# rc-light-controller-tlc5940-lpc812.net
KiCad netlist of a schematic drawn in EAGLE
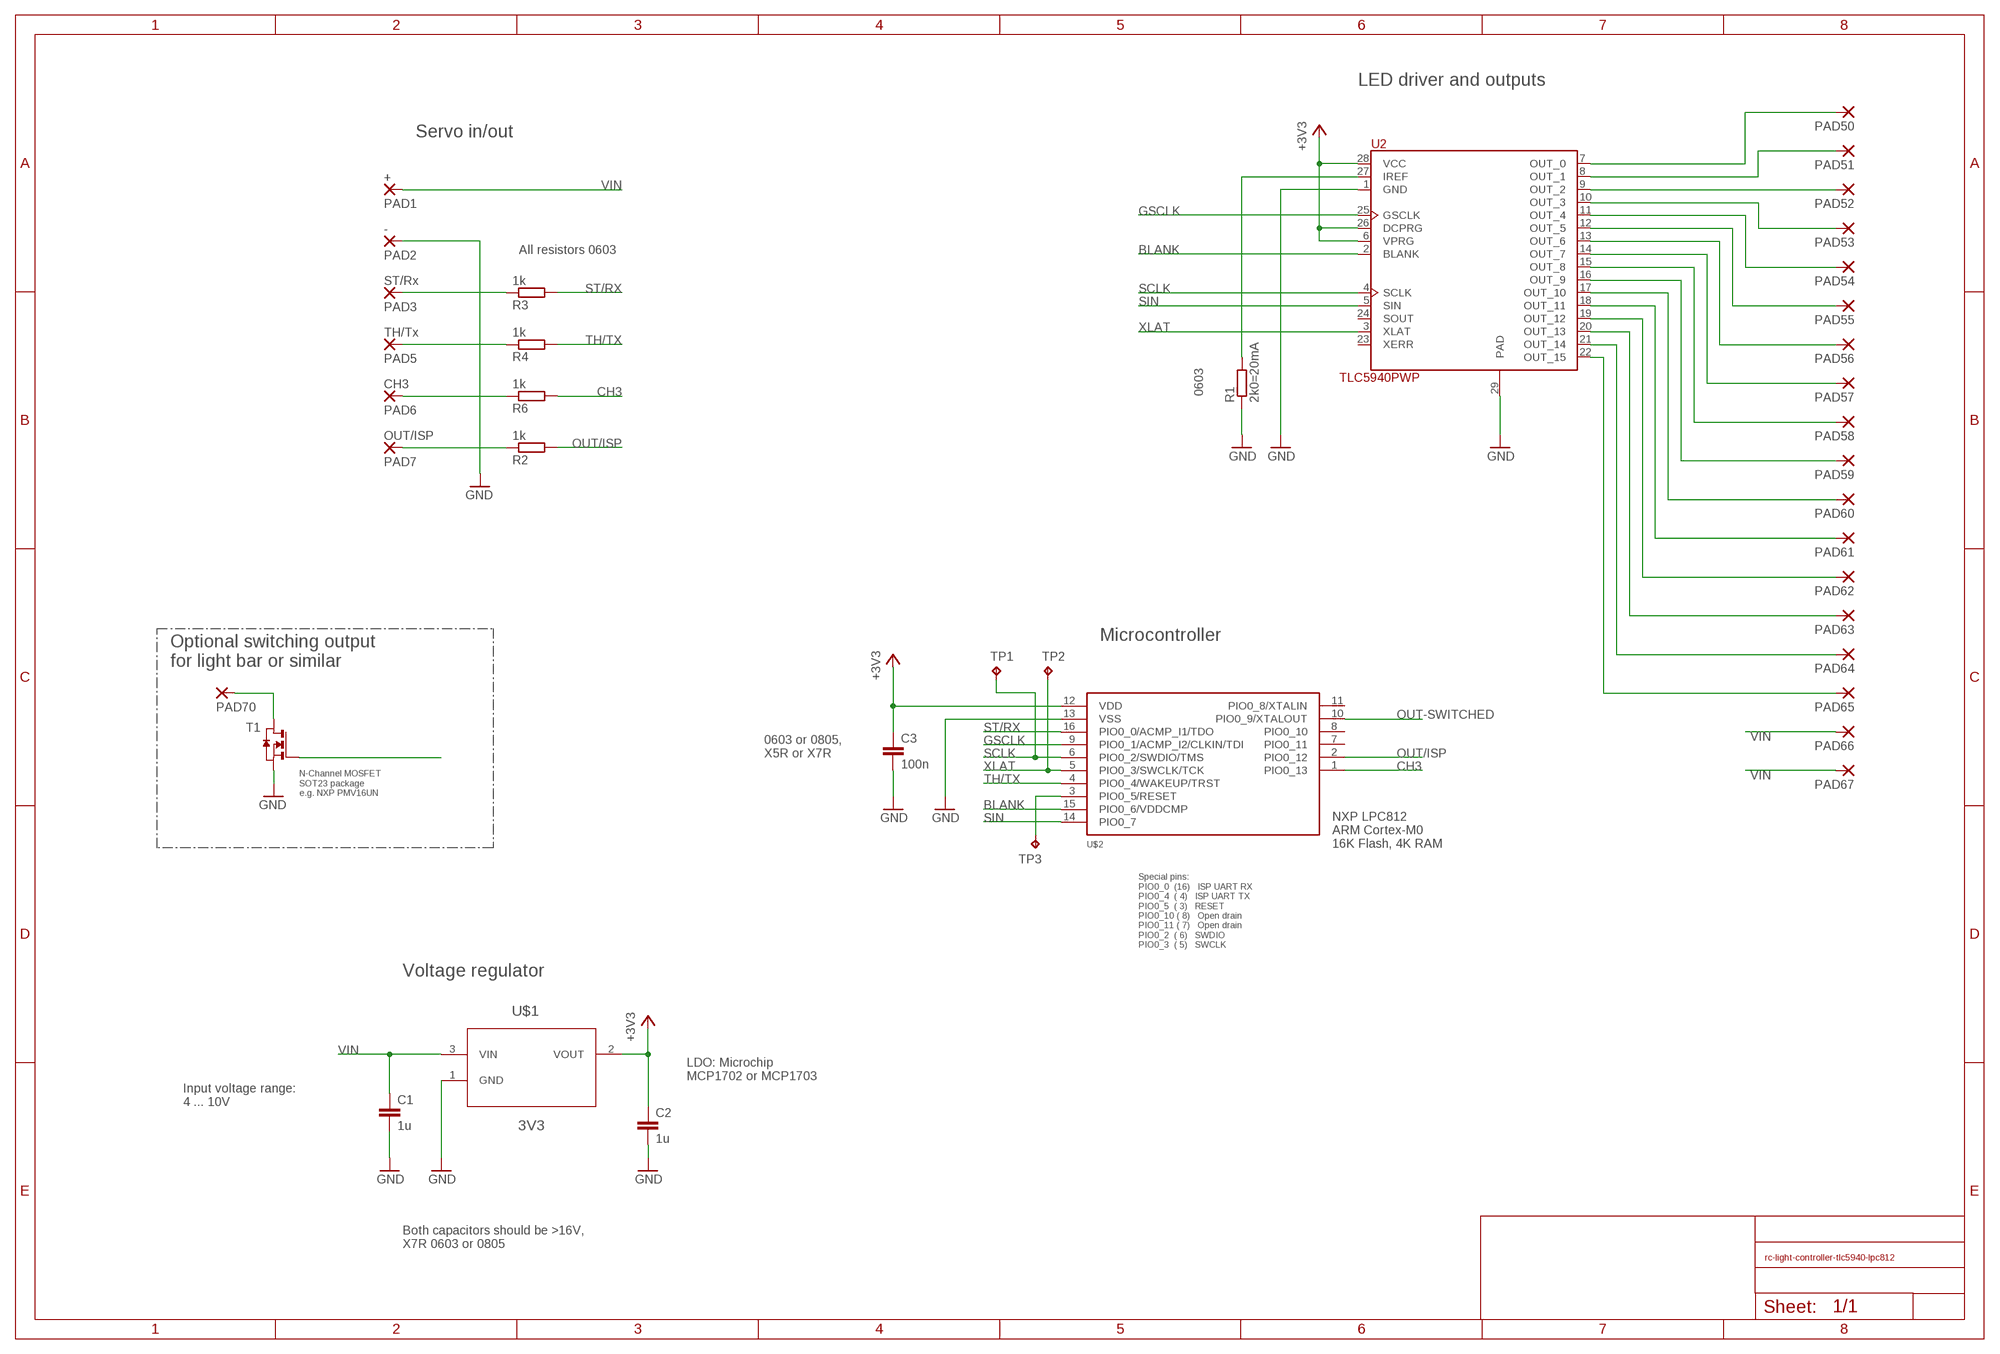
[diagram p0: schematic, sheet 1]

(export (version "E")
  (design (tool "Eeschema 10.0.6"))
  (components
    (comp (ref "C1")
      (value "1u")
      (footprint "eagle-import:C0805")
      (libsource (lib "eagle-import") (part "C-EUC0805"))
    )
    (comp (ref "C2")
      (value "1u")
      (footprint "eagle-import:C0805")
      (libsource (lib "eagle-import") (part "C-EUC0805"))
    )
    (comp (ref "C3")
      (value "100n")
      (footprint "eagle-import:C0805")
      (libsource (lib "eagle-import") (part "C-EUC0805"))
    )
    (comp (ref "PAD1")
      (value "+")
      (footprint "eagle-import:SMD80X120")
      (libsource (lib "eagle-import") (part "SDM80X120"))
    )
    (comp (ref "PAD2")
      (value "-")
      (footprint "eagle-import:SMD80X120")
      (libsource (lib "eagle-import") (part "SDM80X120"))
    )
    (comp (ref "PAD3")
      (value "ST/Rx")
      (footprint "eagle-import:SMD80X120")
      (libsource (lib "eagle-import") (part "SDM80X120"))
    )
    (comp (ref "PAD5")
      (value "TH/Tx")
      (footprint "eagle-import:SMD80X120")
      (libsource (lib "eagle-import") (part "SDM80X120"))
    )
    (comp (ref "PAD6")
      (value "CH3")
      (footprint "eagle-import:SMD80X120")
      (libsource (lib "eagle-import") (part "SDM80X120"))
    )
    (comp (ref "PAD7")
      (value "OUT/ISP")
      (footprint "eagle-import:SMD80X120")
      (libsource (lib "eagle-import") (part "SDM80X120"))
    )
    (comp (ref "PAD50")
      (value "SMD50X100")
      (footprint "eagle-import:SMD50X100")
      (libsource (lib "eagle-import") (part "SMD50X100"))
    )
    (comp (ref "PAD51")
      (value "SMD50X100")
      (footprint "eagle-import:SMD50X100")
      (libsource (lib "eagle-import") (part "SMD50X100"))
    )
    (comp (ref "PAD52")
      (value "SMD50X100")
      (footprint "eagle-import:SMD50X100")
      (libsource (lib "eagle-import") (part "SMD50X100"))
    )
    (comp (ref "PAD53")
      (value "SMD50X100")
      (footprint "eagle-import:SMD50X100")
      (libsource (lib "eagle-import") (part "SMD50X100"))
    )
    (comp (ref "PAD54")
      (value "SMD50X100")
      (footprint "eagle-import:SMD50X100")
      (libsource (lib "eagle-import") (part "SMD50X100"))
    )
    (comp (ref "PAD55")
      (value "SMD50X100")
      (footprint "eagle-import:SMD50X100")
      (libsource (lib "eagle-import") (part "SMD50X100"))
    )
    (comp (ref "PAD56")
      (value "SMD50X100")
      (footprint "eagle-import:SMD50X100")
      (libsource (lib "eagle-import") (part "SMD50X100"))
    )
    (comp (ref "PAD57")
      (value "SMD50X100")
      (footprint "eagle-import:SMD50X100")
      (libsource (lib "eagle-import") (part "SMD50X100"))
    )
    (comp (ref "PAD58")
      (value "SMD50X100")
      (footprint "eagle-import:SMD50X100")
      (libsource (lib "eagle-import") (part "SMD50X100"))
    )
    (comp (ref "PAD59")
      (value "SMD50X100")
      (footprint "eagle-import:SMD50X100")
      (libsource (lib "eagle-import") (part "SMD50X100"))
    )
    (comp (ref "PAD60")
      (value "SMD50X100")
      (footprint "eagle-import:SMD50X100")
      (libsource (lib "eagle-import") (part "SMD50X100"))
    )
    (comp (ref "PAD61")
      (value "SMD50X100")
      (footprint "eagle-import:SMD50X100")
      (libsource (lib "eagle-import") (part "SMD50X100"))
    )
    (comp (ref "PAD62")
      (value "SMD50X100")
      (footprint "eagle-import:SMD50X100")
      (libsource (lib "eagle-import") (part "SMD50X100"))
    )
    (comp (ref "PAD63")
      (value "SMD50X100")
      (footprint "eagle-import:SMD50X100")
      (libsource (lib "eagle-import") (part "SMD50X100"))
    )
    (comp (ref "PAD64")
      (value "SMD50X100")
      (footprint "eagle-import:SMD50X100")
      (libsource (lib "eagle-import") (part "SMD50X100"))
    )
    (comp (ref "PAD65")
      (value "SMD50X100")
      (footprint "eagle-import:SMD50X100")
      (libsource (lib "eagle-import") (part "SMD50X100"))
    )
    (comp (ref "PAD66")
      (value "SMD50X100")
      (footprint "eagle-import:SMD50X100")
      (libsource (lib "eagle-import") (part "SMD50X100"))
    )
    (comp (ref "PAD67")
      (value "SMD50X100")
      (footprint "eagle-import:SMD50X100")
      (libsource (lib "eagle-import") (part "SMD50X100"))
    )
    (comp (ref "PAD70")
      (value "SMD50X100")
      (footprint "eagle-import:SMD50X100")
      (libsource (lib "eagle-import") (part "SMD50X100"))
    )
    (comp (ref "R1")
      (value "2k0=20mA")
      (footprint "eagle-import:R0805")
      (libsource (lib "eagle-import") (part "R-EU_R0805"))
    )
    (comp (ref "R2")
      (value "1k")
      (footprint "eagle-import:R0603")
      (libsource (lib "eagle-import") (part "R-EU_R0603"))
    )
    (comp (ref "R3")
      (value "1k")
      (footprint "eagle-import:R0603")
      (libsource (lib "eagle-import") (part "R-EU_R0603"))
    )
    (comp (ref "R4")
      (value "1k")
      (footprint "eagle-import:R0603")
      (libsource (lib "eagle-import") (part "R-EU_R0603"))
    )
    (comp (ref "R6")
      (value "1k")
      (footprint "eagle-import:R0603")
      (libsource (lib "eagle-import") (part "R-EU_R0603"))
    )
    (comp (ref "T1")
      (value "NMOSSOT23")
      (footprint "eagle-import:SOT-23")
      (libsource (lib "eagle-import") (part "NMOSSOT23"))
    )
    (comp (ref "TP1")
      (value "SWDIO")
      (footprint "eagle-import:TP10R")
      (libsource (lib "eagle-import") (part "TPTP10R"))
    )
    (comp (ref "TP2")
      (value "SWCLK")
      (footprint "eagle-import:TP10R")
      (libsource (lib "eagle-import") (part "TPTP10R"))
    )
    (comp (ref "TP3")
      (value "RESET")
      (footprint "eagle-import:TP10R")
      (libsource (lib "eagle-import") (part "TPTP10R"))
    )
    (comp (ref "U$1")
      (value "3V3")
      (footprint "eagle-import:SOT95P300X145-3N")
      (fields (field (name "MPN") "MCP1703T-3302E/CB"))
      (libsource (lib "eagle-import") (part "MCP1703T-3302E/CB"))
    )
    (comp (ref "U$2")
      (value "LPC812")
      (footprint "eagle-import:TSSOP16")
      (libsource (lib "eagle-import") (part "LPC812M101JDH16"))
    )
    (comp (ref "U2")
      (value "TLC5940PWP")
      (footprint "eagle-import:SOP65P640X120-29N")
      (libsource (lib "eagle-import") (part "TLC5940PWP"))
    )
  )
  (nets
    (net (code "1") (name "+3V3") (class "Default")
      (node (ref "C2") (pin "1") (pinfunction "1_1") (pintype "passive"))
      (node (ref "C3") (pin "1") (pinfunction "1_1") (pintype "passive"))
      (node (ref "U$1") (pin "2") (pinfunction "VOUT_2") (pintype "output"))
      (node (ref "U$2") (pin "12") (pinfunction "VDD_12") (pintype "bidirectional"))
      (node (ref "U2") (pin "26") (pinfunction "DCPRG_26") (pintype "input"))
      (node (ref "U2") (pin "28") (pinfunction "VCC_28") (pintype "power_in"))
      (node (ref "U2") (pin "6") (pinfunction "VPRG_6") (pintype "input"))
    )
    (net (code "2") (name "/BLANK") (class "Default")
      (node (ref "U$2") (pin "15") (pinfunction "PIO0_6/VDDCMP_15") (pintype "bidirectional"))
      (node (ref "U2") (pin "2") (pinfunction "BLANK_2") (pintype "input"))
    )
    (net (code "3") (name "/CH3") (class "Default")
      (node (ref "R6") (pin "2") (pinfunction "2_2") (pintype "passive"))
      (node (ref "U$2") (pin "1") (pinfunction "PIO0_13_1") (pintype "bidirectional"))
    )
    (net (code "4") (name "/GSCLK") (class "Default")
      (node (ref "U$2") (pin "9") (pinfunction "PIO0_1/ACMP_I2/CLKIN/TDI_9") (pintype "bidirectional"))
      (node (ref "U2") (pin "25") (pinfunction "GSCLK_25") (pintype "input"))
    )
    (net (code "5") (name "/OUT-SWITCHED") (class "Default")
      (node (ref "T1") (pin "3") (pinfunction "G_3") (pintype "passive"))
      (node (ref "U$2") (pin "10") (pinfunction "PIO0_9/XTALOUT_10") (pintype "bidirectional"))
    )
    (net (code "6") (name "/OUT{slash}ISP") (class "Default")
      (node (ref "R2") (pin "2") (pinfunction "2_2") (pintype "passive"))
      (node (ref "U$2") (pin "2") (pinfunction "PIO0_12_2") (pintype "bidirectional"))
    )
    (net (code "7") (name "/SCLK") (class "Default")
      (node (ref "TP1") (pin "TP") (pinfunction "TP_TP") (pintype "input"))
      (node (ref "U$2") (pin "6") (pinfunction "PIO0_2/SWDIO/TMS_6") (pintype "bidirectional"))
      (node (ref "U2") (pin "4") (pinfunction "SCLK_4") (pintype "input"))
    )
    (net (code "8") (name "/SIN") (class "Default")
      (node (ref "U$2") (pin "14") (pinfunction "PIO0_7_14") (pintype "bidirectional"))
      (node (ref "U2") (pin "5") (pinfunction "SIN_5") (pintype "input"))
    )
    (net (code "9") (name "/ST{slash}RX") (class "Default")
      (node (ref "R3") (pin "2") (pinfunction "2_2") (pintype "passive"))
      (node (ref "U$2") (pin "16") (pinfunction "PIO0_0/ACMP_I1/TDO_16") (pintype "bidirectional"))
    )
    (net (code "10") (name "/TH{slash}TX") (class "Default")
      (node (ref "R4") (pin "2") (pinfunction "2_2") (pintype "passive"))
      (node (ref "U$2") (pin "4") (pinfunction "PIO0_4/WAKEUP/TRST_4") (pintype "bidirectional"))
    )
    (net (code "11") (name "/VIN") (class "Default")
      (node (ref "C1") (pin "1") (pinfunction "1_1") (pintype "passive"))
      (node (ref "PAD1") (pin "1") (pinfunction "P_1") (pintype "passive"))
      (node (ref "PAD66") (pin "1") (pinfunction "P_1") (pintype "passive"))
      (node (ref "PAD67") (pin "1") (pinfunction "P_1") (pintype "passive"))
      (node (ref "U$1") (pin "3") (pinfunction "VIN_3") (pintype "input"))
    )
    (net (code "12") (name "/XLAT") (class "Default")
      (node (ref "TP2") (pin "TP") (pinfunction "TP_TP") (pintype "input"))
      (node (ref "U$2") (pin "5") (pinfunction "PIO0_3/SWCLK/TCK_5") (pintype "bidirectional"))
      (node (ref "U2") (pin "3") (pinfunction "XLAT_3") (pintype "input"))
    )
    (net (code "13") (name "GND") (class "Default")
      (node (ref "C1") (pin "2") (pinfunction "2_2") (pintype "passive"))
      (node (ref "C2") (pin "2") (pinfunction "2_2") (pintype "passive"))
      (node (ref "C3") (pin "2") (pinfunction "2_2") (pintype "passive"))
      (node (ref "PAD2") (pin "1") (pinfunction "P_1") (pintype "passive"))
      (node (ref "R1") (pin "1") (pinfunction "1_1") (pintype "passive"))
      (node (ref "T1") (pin "2") (pinfunction "S_2") (pintype "passive"))
      (node (ref "U$1") (pin "1") (pinfunction "GND_1") (pintype "passive"))
      (node (ref "U$2") (pin "13") (pinfunction "VSS_13") (pintype "bidirectional"))
      (node (ref "U2") (pin "1") (pinfunction "GND_1") (pintype "power_in"))
      (node (ref "U2") (pin "29") (pinfunction "PAD_29") (pintype "passive"))
    )
    (net (code "14") (name "Net-(PAD3-P)") (class "Default")
      (node (ref "PAD3") (pin "1") (pinfunction "P_1") (pintype "passive"))
      (node (ref "R3") (pin "1") (pinfunction "1_1") (pintype "passive"))
    )
    (net (code "15") (name "Net-(PAD5-P)") (class "Default")
      (node (ref "PAD5") (pin "1") (pinfunction "P_1") (pintype "passive"))
      (node (ref "R4") (pin "1") (pinfunction "1_1") (pintype "passive"))
    )
    (net (code "16") (name "Net-(PAD6-P)") (class "Default")
      (node (ref "PAD6") (pin "1") (pinfunction "P_1") (pintype "passive"))
      (node (ref "R6") (pin "1") (pinfunction "1_1") (pintype "passive"))
    )
    (net (code "17") (name "Net-(PAD7-P)") (class "Default")
      (node (ref "PAD7") (pin "1") (pinfunction "P_1") (pintype "passive"))
      (node (ref "R2") (pin "1") (pinfunction "1_1") (pintype "passive"))
    )
    (net (code "18") (name "Net-(PAD50-P)") (class "Default")
      (node (ref "PAD50") (pin "1") (pinfunction "P_1") (pintype "passive"))
      (node (ref "U2") (pin "7") (pinfunction "OUT_0_7") (pintype "output"))
    )
    (net (code "19") (name "Net-(PAD51-P)") (class "Default")
      (node (ref "PAD51") (pin "1") (pinfunction "P_1") (pintype "passive"))
      (node (ref "U2") (pin "8") (pinfunction "OUT_1_8") (pintype "output"))
    )
    (net (code "20") (name "Net-(PAD52-P)") (class "Default")
      (node (ref "PAD52") (pin "1") (pinfunction "P_1") (pintype "passive"))
      (node (ref "U2") (pin "9") (pinfunction "OUT_2_9") (pintype "output"))
    )
    (net (code "21") (name "Net-(PAD53-P)") (class "Default")
      (node (ref "PAD53") (pin "1") (pinfunction "P_1") (pintype "passive"))
      (node (ref "U2") (pin "10") (pinfunction "OUT_3_10") (pintype "output"))
    )
    (net (code "22") (name "Net-(PAD54-P)") (class "Default")
      (node (ref "PAD54") (pin "1") (pinfunction "P_1") (pintype "passive"))
      (node (ref "U2") (pin "11") (pinfunction "OUT_4_11") (pintype "output"))
    )
    (net (code "23") (name "Net-(PAD55-P)") (class "Default")
      (node (ref "PAD55") (pin "1") (pinfunction "P_1") (pintype "passive"))
      (node (ref "U2") (pin "12") (pinfunction "OUT_5_12") (pintype "output"))
    )
    (net (code "24") (name "Net-(PAD56-P)") (class "Default")
      (node (ref "PAD56") (pin "1") (pinfunction "P_1") (pintype "passive"))
      (node (ref "U2") (pin "13") (pinfunction "OUT_6_13") (pintype "output"))
    )
    (net (code "25") (name "Net-(PAD57-P)") (class "Default")
      (node (ref "PAD57") (pin "1") (pinfunction "P_1") (pintype "passive"))
      (node (ref "U2") (pin "14") (pinfunction "OUT_7_14") (pintype "output"))
    )
    (net (code "26") (name "Net-(PAD58-P)") (class "Default")
      (node (ref "PAD58") (pin "1") (pinfunction "P_1") (pintype "passive"))
      (node (ref "U2") (pin "15") (pinfunction "OUT_8_15") (pintype "output"))
    )
    (net (code "27") (name "Net-(PAD59-P)") (class "Default")
      (node (ref "PAD59") (pin "1") (pinfunction "P_1") (pintype "passive"))
      (node (ref "U2") (pin "16") (pinfunction "OUT_9_16") (pintype "output"))
    )
    (net (code "28") (name "Net-(PAD60-P)") (class "Default")
      (node (ref "PAD60") (pin "1") (pinfunction "P_1") (pintype "passive"))
      (node (ref "U2") (pin "17") (pinfunction "OUT_10_17") (pintype "output"))
    )
    (net (code "29") (name "Net-(PAD61-P)") (class "Default")
      (node (ref "PAD61") (pin "1") (pinfunction "P_1") (pintype "passive"))
      (node (ref "U2") (pin "18") (pinfunction "OUT_11_18") (pintype "output"))
    )
    (net (code "30") (name "Net-(PAD62-P)") (class "Default")
      (node (ref "PAD62") (pin "1") (pinfunction "P_1") (pintype "passive"))
      (node (ref "U2") (pin "19") (pinfunction "OUT_12_19") (pintype "output"))
    )
    (net (code "31") (name "Net-(PAD63-P)") (class "Default")
      (node (ref "PAD63") (pin "1") (pinfunction "P_1") (pintype "passive"))
      (node (ref "U2") (pin "20") (pinfunction "OUT_13_20") (pintype "output"))
    )
    (net (code "32") (name "Net-(PAD64-P)") (class "Default")
      (node (ref "PAD64") (pin "1") (pinfunction "P_1") (pintype "passive"))
      (node (ref "U2") (pin "21") (pinfunction "OUT_14_21") (pintype "output"))
    )
    (net (code "33") (name "Net-(PAD65-P)") (class "Default")
      (node (ref "PAD65") (pin "1") (pinfunction "P_1") (pintype "passive"))
      (node (ref "U2") (pin "22") (pinfunction "OUT_15_22") (pintype "output"))
    )
    (net (code "34") (name "Net-(PAD70-P)") (class "Default")
      (node (ref "PAD70") (pin "1") (pinfunction "P_1") (pintype "passive"))
      (node (ref "T1") (pin "1") (pinfunction "D_1") (pintype "passive"))
    )
    (net (code "35") (name "Net-(U$2-PIO0_5{slash}RESET)") (class "Default")
      (node (ref "TP3") (pin "TP") (pinfunction "TP_TP") (pintype "input"))
      (node (ref "U$2") (pin "3") (pinfunction "PIO0_5/RESET_3") (pintype "bidirectional"))
    )
    (net (code "36") (name "Net-(U2-IREF)") (class "Default")
      (node (ref "R1") (pin "2") (pinfunction "2_2") (pintype "passive"))
      (node (ref "U2") (pin "27") (pinfunction "IREF_27") (pintype "power_in"))
    )
    (net (code "37") (name "unconnected-(U$2-PIO0_8{slash}XTALIN-Pad11)") (class "Default")
      (node (ref "U$2") (pin "11") (pinfunction "PIO0_8/XTALIN_11") (pintype "bidirectional"))
    )
    (net (code "38") (name "unconnected-(U$2-PIO0_10-Pad8)") (class "Default")
      (node (ref "U$2") (pin "8") (pinfunction "PIO0_10_8") (pintype "bidirectional"))
    )
    (net (code "39") (name "unconnected-(U$2-PIO0_11-Pad7)") (class "Default")
      (node (ref "U$2") (pin "7") (pinfunction "PIO0_11_7") (pintype "bidirectional"))
    )
    (net (code "40") (name "unconnected-(U2-SOUT-Pad24)") (class "Default")
      (node (ref "U2") (pin "24") (pinfunction "SOUT_24") (pintype "output"))
    )
    (net (code "41") (name "unconnected-(U2-XERR-Pad23)") (class "Default")
      (node (ref "U2") (pin "23") (pinfunction "XERR_23") (pintype "output"))
    )
  )
)
